# HubsanTXModule.net
KiCad netlist of a schematic drawn in EAGLE
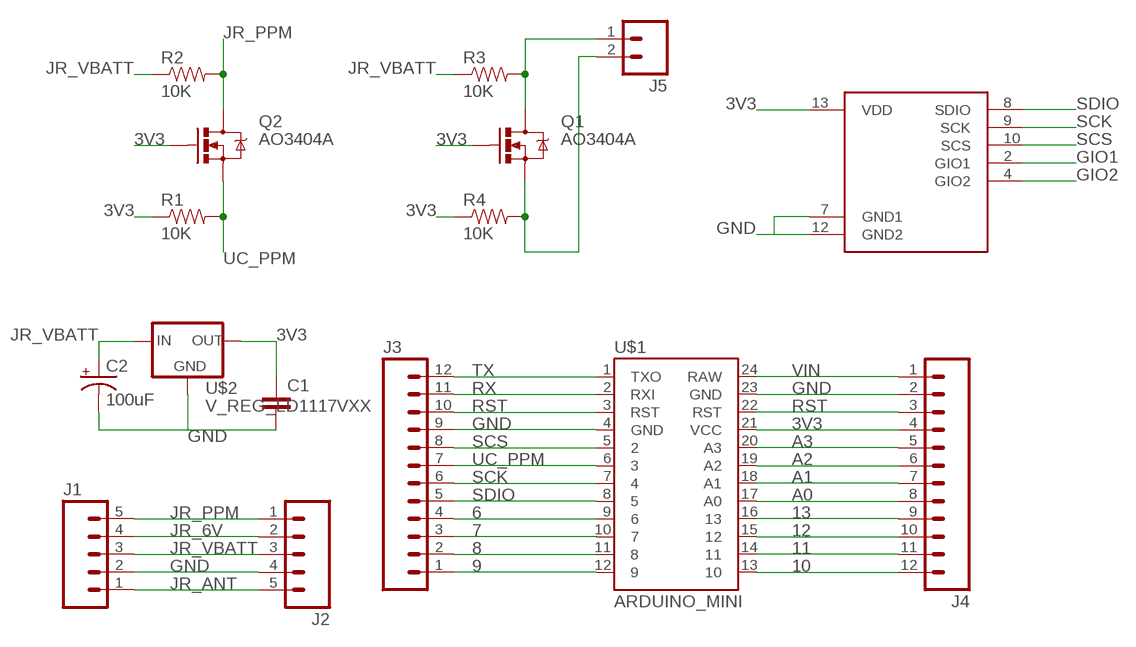
[diagram p0: schematic, sheet 1]

(export (version "E")
  (design (tool "Eeschema 10.0.6"))
  (components
    (comp (ref "C1")
      (value "10UF10V10%(0805)")
      (footprint "eagle-import:0805-CAP")
      (libsource (lib "eagle-import") (part "10UF10V10%(0805)"))
    )
    (comp (ref "C2")
      (value "100uF")
      (footprint "eagle-import:NIC_10X10.5_CAP")
      (libsource (lib "eagle-import") (part "100UF-63V-20%(ELECT)"))
    )
    (comp (ref "J1")
      (value "M05PTH")
      (footprint "eagle-import:1X05")
      (libsource (lib "eagle-import") (part "M05PTH"))
    )
    (comp (ref "J2")
      (value "M05PTH")
      (footprint "eagle-import:1X05")
      (libsource (lib "eagle-import") (part "M05PTH"))
    )
    (comp (ref "J3")
      (value "M12PTH")
      (footprint "eagle-import:1X12")
      (libsource (lib "eagle-import") (part "M12PTH"))
    )
    (comp (ref "J4")
      (value "M12PTH")
      (footprint "eagle-import:1X12")
      (libsource (lib "eagle-import") (part "M12PTH"))
    )
    (comp (ref "J5")
      (value "M02PTH")
      (footprint "eagle-import:1X02")
      (libsource (lib "eagle-import") (part "M02PTH"))
    )
    (comp (ref "Q1")
      (value "AO3404A")
      (footprint "eagle-import:SOT23-3")
      (libsource (lib "eagle-import") (part "MOSFET-NCHANNELAO3404A"))
    )
    (comp (ref "Q2")
      (value "AO3404A")
      (footprint "eagle-import:SOT23-3")
      (libsource (lib "eagle-import") (part "MOSFET-NCHANNELAO3404A"))
    )
    (comp (ref "R1")
      (value "10K")
      (footprint "eagle-import:0603-RES")
      (libsource (lib "eagle-import") (part "10KOHM-1/10W-1%(0603)0603"))
    )
    (comp (ref "R2")
      (value "10K")
      (footprint "eagle-import:0603-RES")
      (libsource (lib "eagle-import") (part "10KOHM-1/10W-1%(0603)0603"))
    )
    (comp (ref "R3")
      (value "10K")
      (footprint "eagle-import:0603-RES")
      (libsource (lib "eagle-import") (part "10KOHM-1/10W-1%(0603)0603"))
    )
    (comp (ref "R4")
      (value "10K")
      (footprint "eagle-import:0603-RES")
      (libsource (lib "eagle-import") (part "10KOHM-1/10W-1%(0603)0603"))
    )
    (comp (ref "U$1")
      (value "ARDUINO_MINI")
      (footprint "eagle-import:ARDUINO_MINI")
      (libsource (lib "eagle-import") (part "ARDUINO_MINI"))
    )
    (comp (ref "U$2")
      (value "V_REG_LD1117VXX")
      (footprint "eagle-import:78XXL")
      (libsource (lib "eagle-import") (part "V_REG_LD1117VXX"))
    )
    (comp (ref "U$3")
      (value "A7105_DEVBOARD")
      (footprint "eagle-import:A7105_DEV1")
      (libsource (lib "eagle-import") (part "A7105_DEVBOARD"))
    )
  )
  (nets
    (net (code "1") (name "/3V3") (class "Default")
      (node (ref "C1") (pin "1") (pinfunction "1_1") (pintype "passive"))
      (node (ref "J4") (pin "4") (pinfunction "4_4") (pintype "passive"))
      (node (ref "Q1") (pin "1") (pinfunction "G_1") (pintype "passive"))
      (node (ref "Q2") (pin "1") (pinfunction "G_1") (pintype "passive"))
      (node (ref "R1") (pin "1") (pinfunction "1_1") (pintype "passive"))
      (node (ref "R4") (pin "1") (pinfunction "1_1") (pintype "passive"))
      (node (ref "U$1") (pin "21") (pinfunction "VCC_21") (pintype "bidirectional"))
      (node (ref "U$2") (pin "GND") (pinfunction "OUT_GND") (pintype "passive"))
      (node (ref "U$3") (pin "13") (pinfunction "VDD_13") (pintype "bidirectional"))
    )
    (net (code "2") (name "/6") (class "Default")
      (node (ref "J3") (pin "4") (pinfunction "4_4") (pintype "passive"))
      (node (ref "U$1") (pin "9") (pinfunction "6_9") (pintype "bidirectional"))
    )
    (net (code "3") (name "/7") (class "Default")
      (node (ref "J3") (pin "3") (pinfunction "3_3") (pintype "passive"))
      (node (ref "U$1") (pin "10") (pinfunction "7_10") (pintype "bidirectional"))
    )
    (net (code "4") (name "/8") (class "Default")
      (node (ref "J3") (pin "2") (pinfunction "2_2") (pintype "passive"))
      (node (ref "U$1") (pin "11") (pinfunction "8_11") (pintype "bidirectional"))
    )
    (net (code "5") (name "/9") (class "Default")
      (node (ref "J3") (pin "1") (pinfunction "1_1") (pintype "passive"))
      (node (ref "U$1") (pin "12") (pinfunction "9_12") (pintype "bidirectional"))
    )
    (net (code "6") (name "/10") (class "Default")
      (node (ref "J4") (pin "12") (pinfunction "12_12") (pintype "passive"))
      (node (ref "U$1") (pin "13") (pinfunction "10_13") (pintype "bidirectional"))
    )
    (net (code "7") (name "/11") (class "Default")
      (node (ref "J4") (pin "11") (pinfunction "11_11") (pintype "passive"))
      (node (ref "U$1") (pin "14") (pinfunction "11_14") (pintype "bidirectional"))
    )
    (net (code "8") (name "/12") (class "Default")
      (node (ref "J4") (pin "10") (pinfunction "10_10") (pintype "passive"))
      (node (ref "U$1") (pin "15") (pinfunction "12_15") (pintype "bidirectional"))
    )
    (net (code "9") (name "/13") (class "Default")
      (node (ref "J4") (pin "9") (pinfunction "9_9") (pintype "passive"))
      (node (ref "U$1") (pin "16") (pinfunction "13_16") (pintype "bidirectional"))
    )
    (net (code "10") (name "/A0") (class "Default")
      (node (ref "J4") (pin "8") (pinfunction "8_8") (pintype "passive"))
      (node (ref "U$1") (pin "17") (pinfunction "A0_17") (pintype "bidirectional"))
    )
    (net (code "11") (name "/A1") (class "Default")
      (node (ref "J4") (pin "7") (pinfunction "7_7") (pintype "passive"))
      (node (ref "U$1") (pin "18") (pinfunction "A1_18") (pintype "bidirectional"))
    )
    (net (code "12") (name "/A2") (class "Default")
      (node (ref "J4") (pin "6") (pinfunction "6_6") (pintype "passive"))
      (node (ref "U$1") (pin "19") (pinfunction "A2_19") (pintype "bidirectional"))
    )
    (net (code "13") (name "/A3") (class "Default")
      (node (ref "J4") (pin "5") (pinfunction "5_5") (pintype "passive"))
      (node (ref "U$1") (pin "20") (pinfunction "A3_20") (pintype "bidirectional"))
    )
    (net (code "14") (name "/GIO1") (class "Default")
      (node (ref "U$3") (pin "2") (pinfunction "GIO1_2") (pintype "bidirectional"))
    )
    (net (code "15") (name "/GIO2") (class "Default")
      (node (ref "U$3") (pin "4") (pinfunction "GIO2_4") (pintype "bidirectional"))
    )
    (net (code "16") (name "/GND") (class "Default")
      (node (ref "C1") (pin "2") (pinfunction "2_2") (pintype "passive"))
      (node (ref "C2") (pin "-") (pinfunction "-_-") (pintype "passive"))
      (node (ref "J1") (pin "2") (pinfunction "2_2") (pintype "passive"))
      (node (ref "J2") (pin "4") (pinfunction "4_4") (pintype "passive"))
      (node (ref "J3") (pin "9") (pinfunction "9_9") (pintype "passive"))
      (node (ref "J4") (pin "2") (pinfunction "2_2") (pintype "passive"))
      (node (ref "U$1") (pin "23") (pinfunction "GND_23") (pintype "bidirectional"))
      (node (ref "U$1") (pin "4") (pinfunction "GND_4") (pintype "bidirectional"))
      (node (ref "U$2") (pin "IN") (pinfunction "GND_IN") (pintype "input"))
      (node (ref "U$3") (pin "12") (pinfunction "GND2_12") (pintype "bidirectional"))
      (node (ref "U$3") (pin "7") (pinfunction "GND1_7") (pintype "bidirectional"))
    )
    (net (code "17") (name "/JR_6V") (class "Default")
      (node (ref "J1") (pin "4") (pinfunction "4_4") (pintype "passive"))
      (node (ref "J2") (pin "2") (pinfunction "2_2") (pintype "passive"))
    )
    (net (code "18") (name "/JR_ANT") (class "Default")
      (node (ref "J1") (pin "1") (pinfunction "1_1") (pintype "passive"))
      (node (ref "J2") (pin "5") (pinfunction "5_5") (pintype "passive"))
    )
    (net (code "19") (name "/JR_PPM") (class "Default")
      (node (ref "J1") (pin "5") (pinfunction "5_5") (pintype "passive"))
      (node (ref "J2") (pin "1") (pinfunction "1_1") (pintype "passive"))
      (node (ref "Q2") (pin "3") (pinfunction "D_3") (pintype "passive"))
      (node (ref "R2") (pin "2") (pinfunction "2_2") (pintype "passive"))
    )
    (net (code "20") (name "/JR_VBATT") (class "Default")
      (node (ref "C2") (pin "+") (pinfunction "+_+") (pintype "passive"))
      (node (ref "J1") (pin "3") (pinfunction "3_3") (pintype "passive"))
      (node (ref "J2") (pin "3") (pinfunction "3_3") (pintype "passive"))
      (node (ref "R2") (pin "1") (pinfunction "1_1") (pintype "passive"))
      (node (ref "R3") (pin "1") (pinfunction "1_1") (pintype "passive"))
      (node (ref "U$2") (pin "OUT") (pinfunction "IN_OUT") (pintype "input"))
    )
    (net (code "21") (name "/RST") (class "Default")
      (node (ref "J3") (pin "10") (pinfunction "10_10") (pintype "passive"))
      (node (ref "J4") (pin "3") (pinfunction "3_3") (pintype "passive"))
      (node (ref "U$1") (pin "22") (pinfunction "RST_22") (pintype "bidirectional"))
      (node (ref "U$1") (pin "3") (pinfunction "RST_3") (pintype "bidirectional"))
    )
    (net (code "22") (name "/RX") (class "Default")
      (node (ref "J3") (pin "11") (pinfunction "11_11") (pintype "passive"))
      (node (ref "U$1") (pin "2") (pinfunction "RXI_2") (pintype "bidirectional"))
    )
    (net (code "23") (name "/SCK") (class "Default")
      (node (ref "J3") (pin "6") (pinfunction "6_6") (pintype "passive"))
      (node (ref "U$1") (pin "7") (pinfunction "4_7") (pintype "bidirectional"))
      (node (ref "U$3") (pin "9") (pinfunction "SCK_9") (pintype "bidirectional"))
    )
    (net (code "24") (name "/SCS") (class "Default")
      (node (ref "J3") (pin "8") (pinfunction "8_8") (pintype "passive"))
      (node (ref "U$1") (pin "5") (pinfunction "2_5") (pintype "bidirectional"))
      (node (ref "U$3") (pin "10") (pinfunction "SCS_10") (pintype "bidirectional"))
    )
    (net (code "25") (name "/SDIO") (class "Default")
      (node (ref "J3") (pin "5") (pinfunction "5_5") (pintype "passive"))
      (node (ref "U$1") (pin "8") (pinfunction "5_8") (pintype "bidirectional"))
      (node (ref "U$3") (pin "8") (pinfunction "SDIO_8") (pintype "bidirectional"))
    )
    (net (code "26") (name "/TX") (class "Default")
      (node (ref "J3") (pin "12") (pinfunction "12_12") (pintype "passive"))
      (node (ref "U$1") (pin "1") (pinfunction "TXO_1") (pintype "bidirectional"))
    )
    (net (code "27") (name "/UC_PPM") (class "Default")
      (node (ref "J3") (pin "7") (pinfunction "7_7") (pintype "passive"))
      (node (ref "Q2") (pin "2") (pinfunction "S_2") (pintype "passive"))
      (node (ref "R1") (pin "2") (pinfunction "2_2") (pintype "passive"))
      (node (ref "U$1") (pin "6") (pinfunction "3_6") (pintype "bidirectional"))
    )
    (net (code "28") (name "/VIN") (class "Default")
      (node (ref "J4") (pin "1") (pinfunction "1_1") (pintype "passive"))
      (node (ref "U$1") (pin "24") (pinfunction "RAW_24") (pintype "bidirectional"))
    )
    (net (code "29") (name "Net-(Q1-D)") (class "Default")
      (node (ref "J5") (pin "1") (pinfunction "1_1") (pintype "passive"))
      (node (ref "Q1") (pin "3") (pinfunction "D_3") (pintype "passive"))
      (node (ref "R3") (pin "2") (pinfunction "2_2") (pintype "passive"))
    )
    (net (code "30") (name "Net-(Q1-S)") (class "Default")
      (node (ref "J5") (pin "2") (pinfunction "2_2") (pintype "passive"))
      (node (ref "Q1") (pin "2") (pinfunction "S_2") (pintype "passive"))
      (node (ref "R4") (pin "2") (pinfunction "2_2") (pintype "passive"))
    )
  )
)
